# rflink-litev06.net
KiCad netlist of a schematic drawn in EAGLE
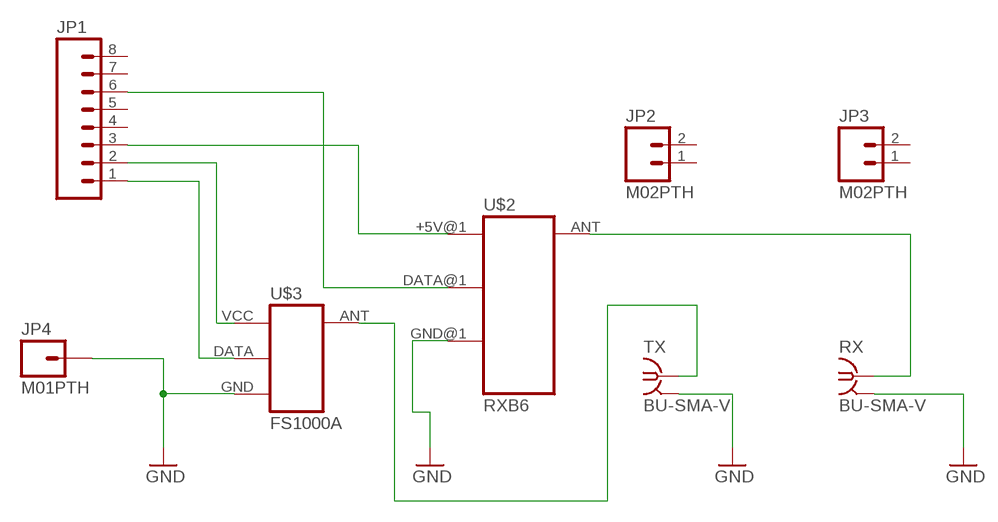
[diagram p0: schematic, sheet 1]

(export (version "E")
  (design (tool "Eeschema 10.0.6"))
  (components
    (comp (ref "JP1")
      (value "M081X08")
      (footprint "eagle-import:1X08")
      (libsource (lib "eagle-import") (part "M081X08"))
    )
    (comp (ref "JP2")
      (value "M02PTH")
      (footprint "eagle-import:1X02")
      (libsource (lib "eagle-import") (part "M02PTH"))
    )
    (comp (ref "JP3")
      (value "M02PTH")
      (footprint "eagle-import:1X02")
      (libsource (lib "eagle-import") (part "M02PTH"))
    )
    (comp (ref "JP4")
      (value "M01PTH")
      (footprint "eagle-import:1X01")
      (libsource (lib "eagle-import") (part "M01PTH"))
    )
    (comp (ref "RX")
      (value "BU-SMA-V")
      (footprint "eagle-import:BU-SMA-V")
      (libsource (lib "eagle-import") (part "BU-SMA-V"))
    )
    (comp (ref "TX")
      (value "BU-SMA-V")
      (footprint "eagle-import:BU-SMA-V")
      (libsource (lib "eagle-import") (part "BU-SMA-V"))
    )
    (comp (ref "U$2")
      (value "RXB6")
      (footprint "eagle-import:RF-LINK_RX")
      (libsource (lib "eagle-import") (part "RF-LINK_RX"))
    )
    (comp (ref "U$3")
      (value "FS1000A")
      (footprint "eagle-import:RF-LINK_TX")
      (libsource (lib "eagle-import") (part "RF-LINK_TX"))
    )
  )
  (nets
    (net (code "1") (name "GND") (class "Default")
      (node (ref "JP4") (pin "1") (pinfunction "1_1") (pintype "passive"))
      (node (ref "RX") (pin "2") (pinfunction "2_2") (pintype "passive"))
      (node (ref "RX") (pin "3") (pinfunction "2_3") (pintype "passive"))
      (node (ref "RX") (pin "4") (pinfunction "2_4") (pintype "passive"))
      (node (ref "RX") (pin "5") (pinfunction "2_5") (pintype "passive"))
      (node (ref "TX") (pin "2") (pinfunction "2_2") (pintype "passive"))
      (node (ref "TX") (pin "3") (pinfunction "2_3") (pintype "passive"))
      (node (ref "TX") (pin "4") (pinfunction "2_4") (pintype "passive"))
      (node (ref "TX") (pin "5") (pinfunction "2_5") (pintype "passive"))
      (node (ref "U$2") (pin "GND@1") (pinfunction "GND_GND@1") (pintype "power_in"))
      (node (ref "U$3") (pin "GND") (pinfunction "GND_GND") (pintype "power_in"))
    )
    (net (code "2") (name "Net-(JP1-Pad1)") (class "Default")
      (node (ref "JP1") (pin "1") (pinfunction "1_1") (pintype "passive"))
      (node (ref "U$3") (pin "DATA") (pinfunction "DATA_DATA") (pintype "input"))
    )
    (net (code "3") (name "Net-(RX-Pad1)") (class "Default")
      (node (ref "RX") (pin "1") (pinfunction "1_1") (pintype "passive"))
      (node (ref "U$2") (pin "ANT") (pinfunction "ANT_ANT") (pintype "passive"))
    )
    (net (code "4") (name "Net-(TX-Pad1)") (class "Default")
      (node (ref "TX") (pin "1") (pinfunction "1_1") (pintype "passive"))
      (node (ref "U$3") (pin "ANT") (pinfunction "ANT_ANT") (pintype "passive"))
    )
    (net (code "5") (name "Net-(U$2-+5V)") (class "Default")
      (node (ref "JP1") (pin "3") (pinfunction "3_3") (pintype "passive"))
      (node (ref "U$2") (pin "+5V@1") (pinfunction "+5V_+5V@1") (pintype "power_in"))
    )
    (net (code "6") (name "Net-(U$2-DATA)") (class "Default")
      (node (ref "JP1") (pin "6") (pinfunction "6_6") (pintype "passive"))
      (node (ref "U$2") (pin "DATA@1") (pinfunction "DATA_DATA@1") (pintype "input"))
    )
    (net (code "7") (name "Net-(U$3-+5V)") (class "Default")
      (node (ref "JP1") (pin "2") (pinfunction "2_2") (pintype "passive"))
      (node (ref "U$3") (pin "VCC") (pinfunction "+5V_VCC") (pintype "power_in"))
    )
    (net (code "8") (name "unconnected-(JP1-Pad4)") (class "Default")
      (node (ref "JP1") (pin "4") (pinfunction "4_4") (pintype "passive"))
    )
    (net (code "9") (name "unconnected-(JP1-Pad5)") (class "Default")
      (node (ref "JP1") (pin "5") (pinfunction "5_5") (pintype "passive"))
    )
    (net (code "10") (name "unconnected-(JP1-Pad7)") (class "Default")
      (node (ref "JP1") (pin "7") (pinfunction "7_7") (pintype "passive"))
    )
    (net (code "11") (name "unconnected-(JP1-Pad8)") (class "Default")
      (node (ref "JP1") (pin "8") (pinfunction "8_8") (pintype "passive"))
    )
    (net (code "12") (name "unconnected-(JP2-Pad1)") (class "Default")
      (node (ref "JP2") (pin "1") (pinfunction "1_1") (pintype "passive"))
    )
    (net (code "13") (name "unconnected-(JP2-Pad2)") (class "Default")
      (node (ref "JP2") (pin "2") (pinfunction "2_2") (pintype "passive"))
    )
    (net (code "14") (name "unconnected-(JP3-Pad1)") (class "Default")
      (node (ref "JP3") (pin "1") (pinfunction "1_1") (pintype "passive"))
    )
    (net (code "15") (name "unconnected-(JP3-Pad2)") (class "Default")
      (node (ref "JP3") (pin "2") (pinfunction "2_2") (pintype "passive"))
    )
  )
)
